# OSO-SCAP-A1-02_SAMD51_Sensor_Cap_WIP.net
KiCad netlist of a schematic drawn in EAGLE
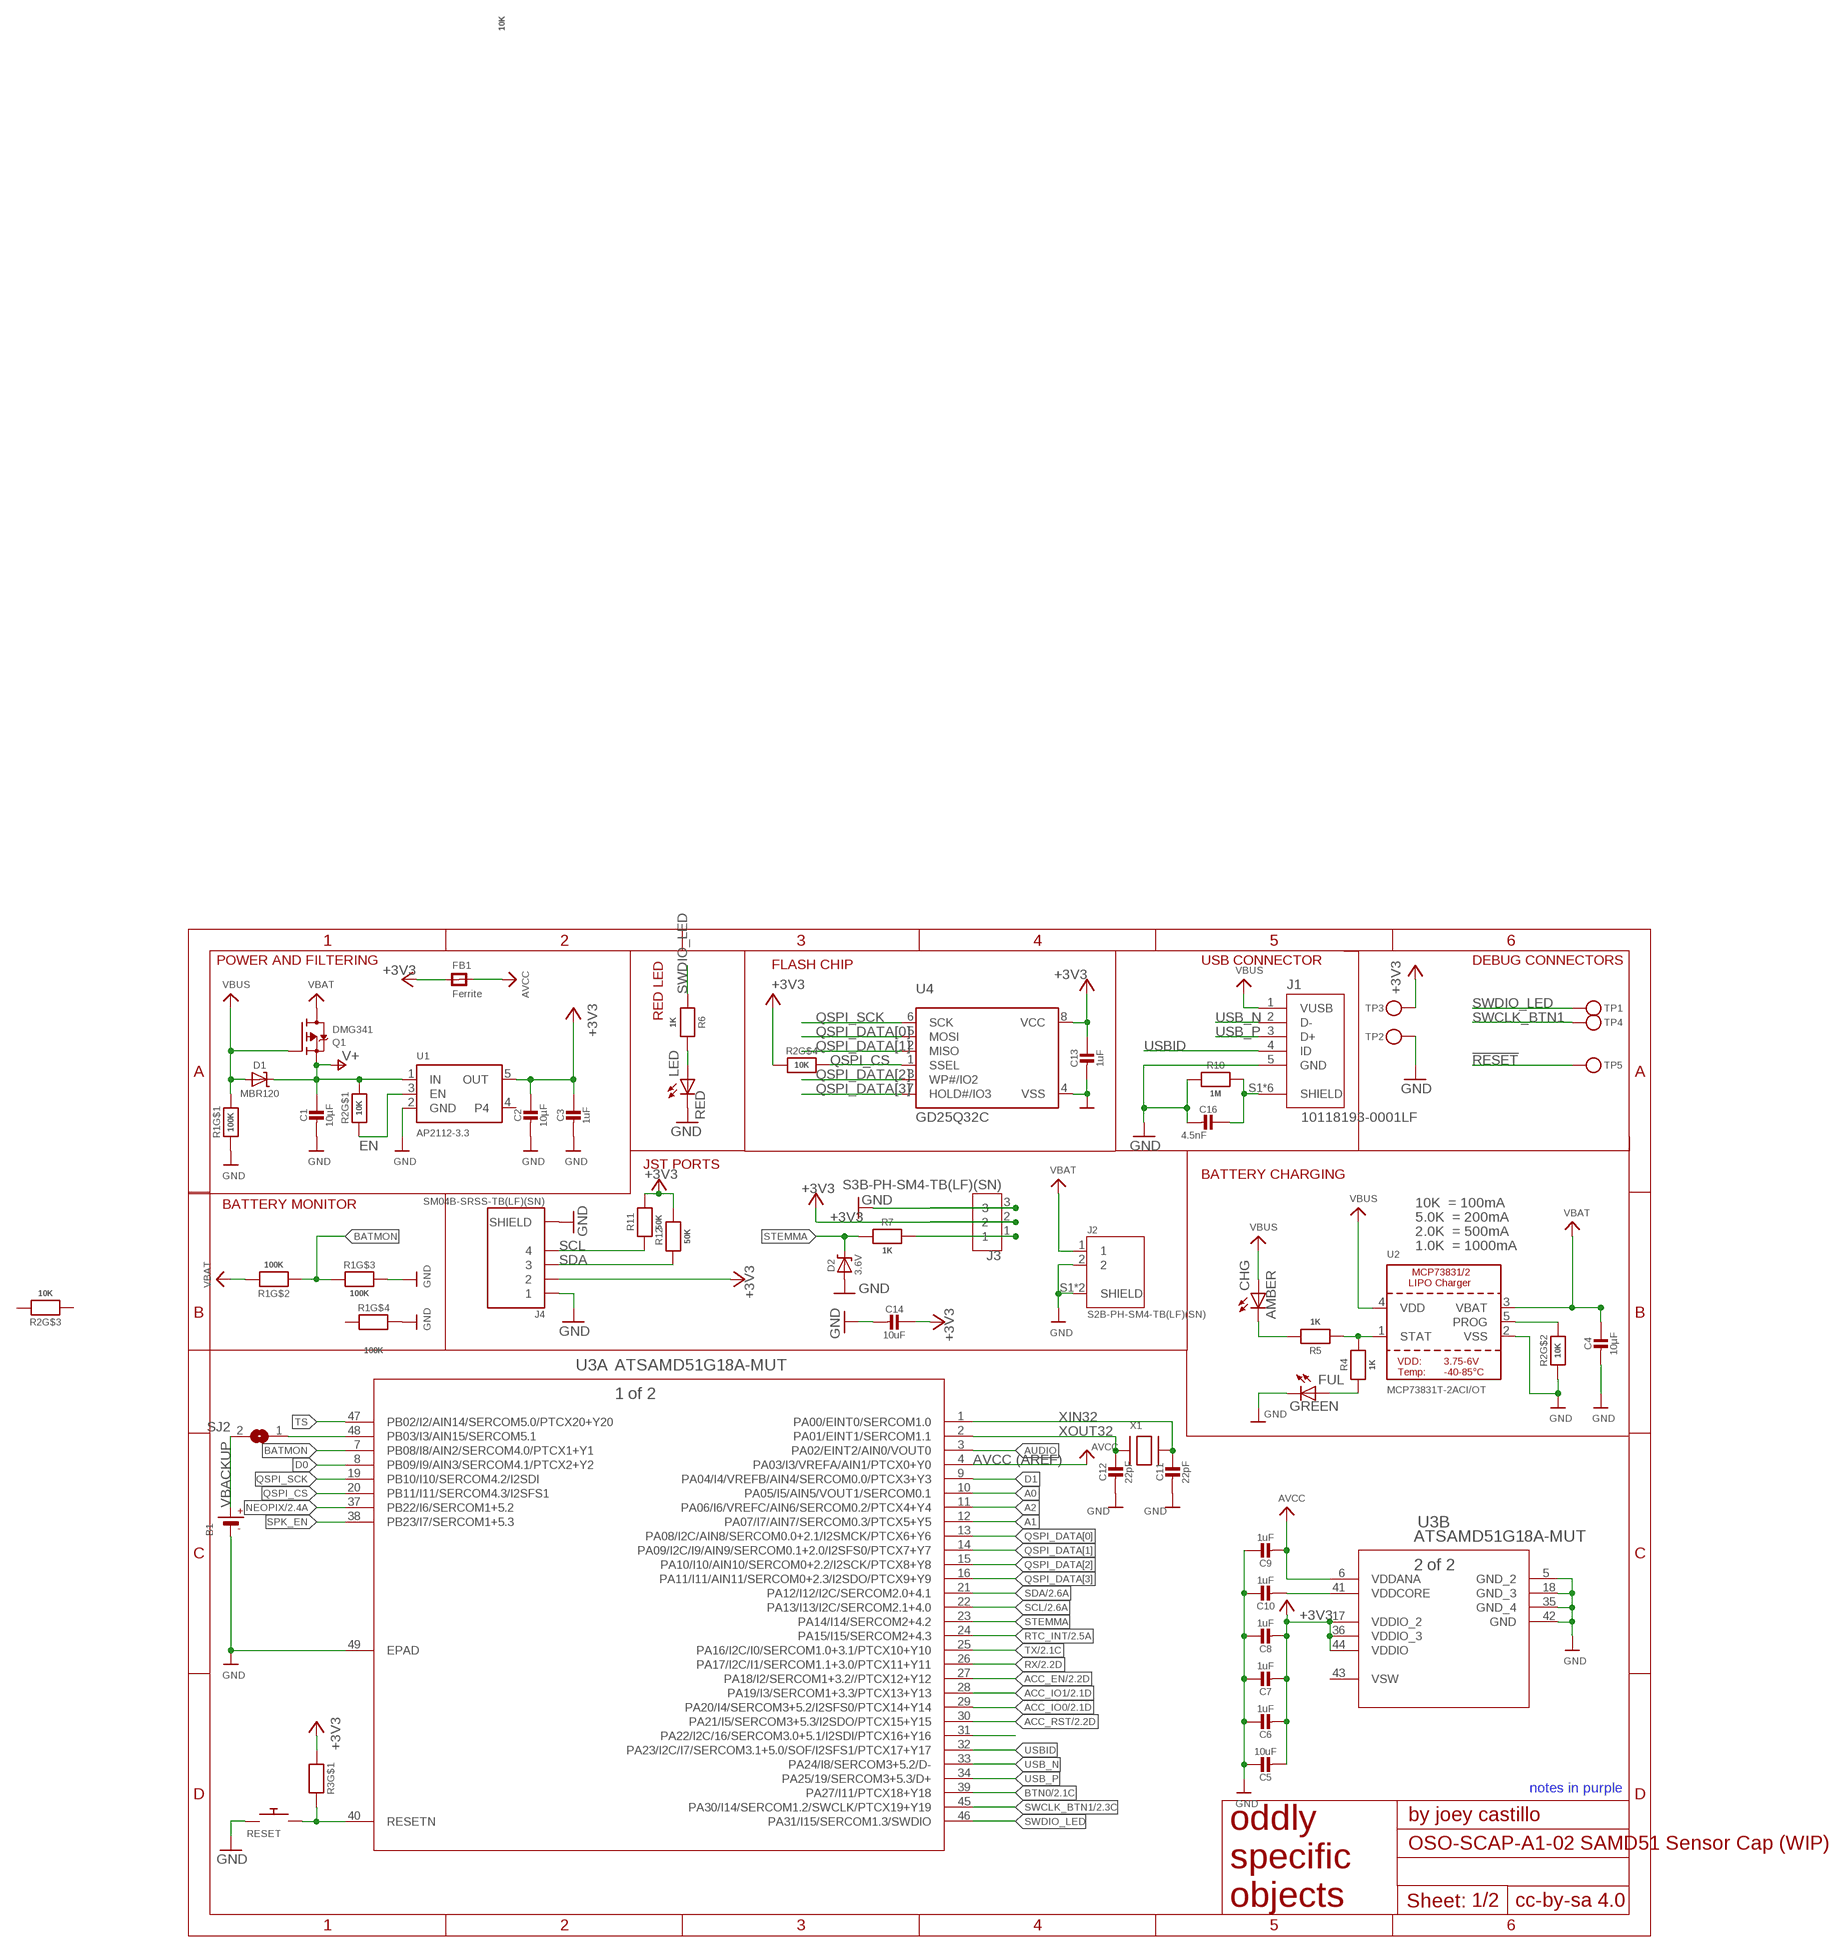
[diagram p0: schematic, sheet 1]
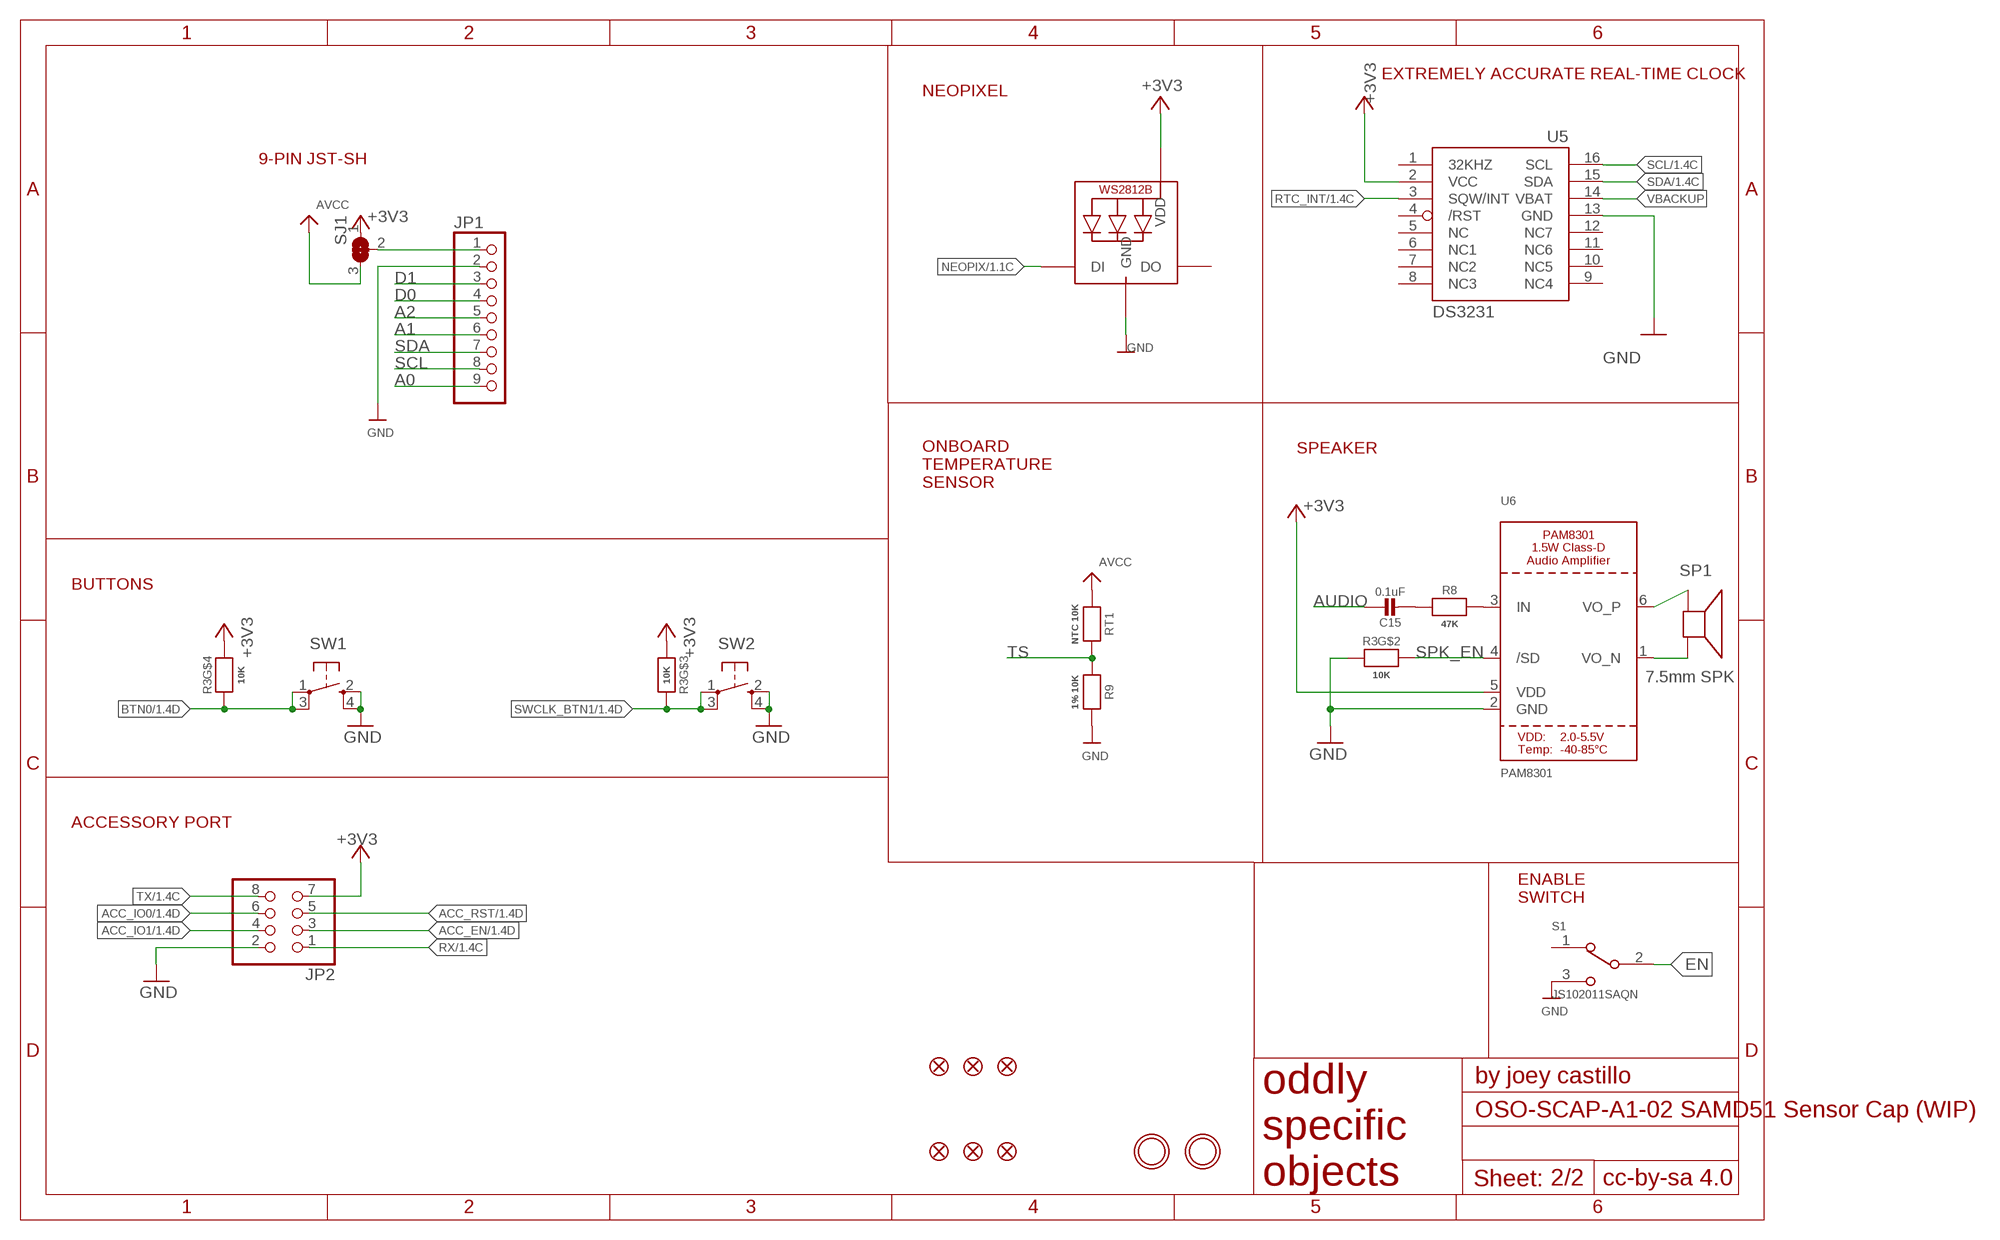
[diagram p1: schematic, sheet 2]

(export (version "E")
  (design (tool "Eeschema 10.0.6"))
  (components
    (comp (ref "B1")
      (value "CR1220")
      (footprint "eagle-import:CR1220-2")
      (libsource (lib "eagle-import") (part "BATTERYCR1220_2"))
    )
    (comp (ref "C1")
      (value "10µF")
      (footprint "eagle-import:0805-NO")
      (libsource (lib "eagle-import") (part "CAP_CERAMIC0805-NOOUTLINE"))
    )
    (comp (ref "C2")
      (value "10µF")
      (footprint "eagle-import:0805-NO")
      (libsource (lib "eagle-import") (part "CAP_CERAMIC0805-NOOUTLINE"))
    )
    (comp (ref "C3")
      (value "1uF")
      (footprint "eagle-import:0805-NO")
      (libsource (lib "eagle-import") (part "CAP_CERAMIC0805-NOOUTLINE"))
    )
    (comp (ref "C4")
      (value "10µF")
      (footprint "eagle-import:0805-NO")
      (libsource (lib "eagle-import") (part "CAP_CERAMIC0805-NOOUTLINE"))
    )
    (comp (ref "C5")
      (value "10uF")
      (footprint "eagle-import:0805_10MGAP")
      (libsource (lib "eagle-import") (part "CAP_CERAMIC0805_10MGAP"))
    )
    (comp (ref "C6")
      (value "1uF")
      (footprint "eagle-import:0805-NO")
      (libsource (lib "eagle-import") (part "CAP_CERAMIC0805-NOOUTLINE"))
    )
    (comp (ref "C7")
      (value "1uF")
      (footprint "eagle-import:0805-NO")
      (libsource (lib "eagle-import") (part "CAP_CERAMIC0805-NOOUTLINE"))
    )
    (comp (ref "C8")
      (value "1uF")
      (footprint "eagle-import:0805-NO")
      (libsource (lib "eagle-import") (part "CAP_CERAMIC0805-NOOUTLINE"))
    )
    (comp (ref "C9")
      (value "1uF")
      (footprint "eagle-import:0805_10MGAP")
      (libsource (lib "eagle-import") (part "CAP_CERAMIC0805_10MGAP"))
    )
    (comp (ref "C10")
      (value "1uF")
      (footprint "eagle-import:0805_10MGAP")
      (libsource (lib "eagle-import") (part "CAP_CERAMIC0805_10MGAP"))
    )
    (comp (ref "C11")
      (value "22pF")
      (footprint "eagle-import:0805-NO")
      (libsource (lib "eagle-import") (part "CAP_CERAMIC0805-NOOUTLINE"))
    )
    (comp (ref "C12")
      (value "22pF")
      (footprint "eagle-import:0805-NO")
      (libsource (lib "eagle-import") (part "CAP_CERAMIC0805-NOOUTLINE"))
    )
    (comp (ref "C13")
      (value "1uF")
      (footprint "eagle-import:0805-NO")
      (libsource (lib "eagle-import") (part "CAP_CERAMIC0805-NOOUTLINE"))
    )
    (comp (ref "C14")
      (value "10uF")
      (footprint "eagle-import:0805-NO")
      (libsource (lib "eagle-import") (part "CAP_CERAMIC0805-NOOUTLINE"))
    )
    (comp (ref "C16")
      (value "4.5nF")
      (footprint "eagle-import:0805-NO")
      (libsource (lib "eagle-import") (part "CAP_CERAMIC0805-NOOUTLINE"))
    )
    (comp (ref "CHG")
      (value "AMBER")
      (footprint "eagle-import:CHIPLED_0603")
      (libsource (lib "eagle-import") (part "LEDCHIPLED_0603"))
    )
    (comp (ref "D1")
      (value "MBR120")
      (footprint "eagle-import:SOD-123")
      (libsource (lib "eagle-import") (part "DIODE-SCHOTTKYSOD-123"))
    )
    (comp (ref "D2")
      (value "3.6V")
      (footprint "eagle-import:SOD-123")
      (libsource (lib "eagle-import") (part "DIODE-ZENERSOD123"))
    )
    (comp (ref "FB1")
      (value "Ferrite")
      (footprint "eagle-import:_0805MP")
      (libsource (lib "eagle-import") (part "FERRITE_0805MP"))
    )
    (comp (ref "FUL")
      (value "GREEN")
      (footprint "eagle-import:CHIPLED_0603")
      (libsource (lib "eagle-import") (part "LEDCHIPLED_0603"))
    )
    (comp (ref "J1")
      (value "10118193-0001LF")
      (footprint "eagle-import:FCI_10118193-0001LF")
      (fields (field (name "DIGI-KEY_PART_NUMBER") "609-4616-1-ND") (field (name "MF") "Amphenol ICC"))
      (libsource (lib "eagle-import") (part "10118193-0001LF"))
    )
    (comp (ref "J2")
      (value "S2B-PH-SM4-TB(LF)(SN)")
      (footprint "eagle-import:JST_S2B-PH-SM4-TB(LF)(SN)")
      (fields
        (field (name "DIGI-KEY_PART_NUMBER") "455-1749-1-ND")
        (field (name "MF") "JST Sales")
        (field (name "MP") "S2B-PH-SM4-TB_LF__SN_")
      )
      (libsource (lib "eagle-import") (part "S2B-PH-SM4-TB(LF)(SN)"))
    )
    (comp (ref "J3")
      (value "S3B-PH-SM4-TB(LF)(SN)")
      (footprint "eagle-import:JST_S3B-PH-SM4-TB(LF)(SN)")
      (fields
        (field (name "DIGI-KEY_PART_NUMBER") "455-1750-1-ND")
        (field (name "MF") "JST Sales")
        (field (name "MP") "S3B-PH-SM4-TB_LF__SN_")
      )
      (libsource (lib "eagle-import") (part "S3B-PH-SM4-TB(LF)(SN)"))
    )
    (comp (ref "J4")
      (value "SM04B-SRSS-TB(LF)(SN)")
      (footprint "eagle-import:JST_SM04B-SRSS-TB(LF)(SN)")
      (fields
        (field (name "DIGI-KEY_PART_NUMBER") "455-1804-1-ND")
        (field (name "MF") "JST Sales")
        (field (name "MP") "SM04B-SRSS-TB_LF__SN_")
      )
      (libsource (lib "eagle-import") (part "SM04B-SRSS-TB(LF)(SN)"))
    )
    (comp (ref "LED")
      (value "RED")
      (footprint "eagle-import:CHIPLED_0805")
      (libsource (lib "eagle-import") (part "LEDCHIPLED_0805"))
    )
    (comp (ref "Q1")
      (value "DMG341")
      (footprint "eagle-import:SOT23-R")
      (libsource (lib "eagle-import") (part "MOSFET-P"))
    )
    (comp (ref "R1")
      (value "100K")
      (footprint "eagle-import:EXBV8V")
      (fields (field (name "MANUFACTURER_PART_NUMBER") "EXBV8V103JV"))
      (libsource (lib "eagle-import") (part "EXB-V8V103JV-GOOD"))
    )
    (comp (ref "R2")
      (value "10K")
      (footprint "eagle-import:EXBV8V")
      (fields (field (name "MANUFACTURER_PART_NUMBER") "EXBV8V103JV"))
      (libsource (lib "eagle-import") (part "EXB-V8V103JV-GOOD"))
    )
    (comp (ref "R3")
      (value "10K")
      (footprint "eagle-import:EXBV8V")
      (fields (field (name "MANUFACTURER_PART_NUMBER") "EXBV8V103JV"))
      (libsource (lib "eagle-import") (part "EXB-V8V103JV-GOOD"))
    )
    (comp (ref "R4")
      (value "1K")
      (footprint "eagle-import:0805-NO")
      (libsource (lib "eagle-import") (part "RESISTOR0805_NOOUTLINE"))
    )
    (comp (ref "R5")
      (value "1K")
      (footprint "eagle-import:0805-NO")
      (libsource (lib "eagle-import") (part "RESISTOR0805_NOOUTLINE"))
    )
    (comp (ref "R6")
      (value "1K")
      (footprint "eagle-import:0805-NO")
      (libsource (lib "eagle-import") (part "RESISTOR0805_NOOUTLINE"))
    )
    (comp (ref "R7")
      (value "1K")
      (footprint "eagle-import:0805-NO")
      (libsource (lib "eagle-import") (part "RESISTOR0805_NOOUTLINE"))
    )
    (comp (ref "R10")
      (value "1M")
      (footprint "eagle-import:0805-NO")
      (libsource (lib "eagle-import") (part "RESISTOR0805_NOOUTLINE"))
    )
    (comp (ref "R11")
      (value "50K")
      (footprint "eagle-import:0805-NO")
      (libsource (lib "eagle-import") (part "RESISTOR0805_NOOUTLINE"))
    )
    (comp (ref "R12")
      (value "50K")
      (footprint "eagle-import:0805-NO")
      (libsource (lib "eagle-import") (part "RESISTOR0805_NOOUTLINE"))
    )
    (comp (ref "RESET")
      (value "SWITCH_PUSHBUTTONC&K_KSS")
      (footprint "eagle-import:BTN_CK_KSS")
      (libsource (lib "eagle-import") (part "SWITCH_PUSHBUTTONC&K_KSS"))
    )
    (comp (ref "SJ2")
      (value "SOLDERJUMPERREFLOW_NOPASTE")
      (footprint "eagle-import:SOLDERJUMPER_REFLOW_NOPASTE")
      (libsource (lib "eagle-import") (part "SOLDERJUMPERREFLOW_NOPASTE"))
    )
    (comp (ref "TP1")
      (value "TESTPOINTROUND1.5MMNO")
      (footprint "eagle-import:TESTPOINT_ROUND_1.5MM_NO")
      (libsource (lib "eagle-import") (part "TESTPOINTROUND1.5MMNO"))
    )
    (comp (ref "TP2")
      (value "TESTPOINTROUND1.5MMNO")
      (footprint "eagle-import:TESTPOINT_ROUND_1.5MM_NO")
      (libsource (lib "eagle-import") (part "TESTPOINTROUND1.5MMNO"))
    )
    (comp (ref "TP3")
      (value "TESTPOINTROUND1.5MMNO")
      (footprint "eagle-import:TESTPOINT_ROUND_1.5MM_NO")
      (libsource (lib "eagle-import") (part "TESTPOINTROUND1.5MMNO"))
    )
    (comp (ref "TP4")
      (value "TESTPOINTROUND1.5MMNO")
      (footprint "eagle-import:TESTPOINT_ROUND_1.5MM_NO")
      (libsource (lib "eagle-import") (part "TESTPOINTROUND1.5MMNO"))
    )
    (comp (ref "TP5")
      (value "TESTPOINTROUND1.5MMNO")
      (footprint "eagle-import:TESTPOINT_ROUND_1.5MM_NO")
      (libsource (lib "eagle-import") (part "TESTPOINTROUND1.5MMNO"))
    )
    (comp (ref "U1")
      (value "AP2112-3.3")
      (footprint "eagle-import:SOT23-5")
      (libsource (lib "eagle-import") (part "VREG_SOT23-5"))
    )
    (comp (ref "U2")
      (value "MCP73831T-2ACI/OT")
      (footprint "eagle-import:SOT23-5")
      (libsource (lib "eagle-import") (part "MCP73831/2"))
    )
    (comp (ref "U3")
      (value "ATSAMD51G18A-MUT")
      (footprint "eagle-import:QFN48_7X7MC")
      (fields (field (name "COPYRIGHT") "Copyright (C) 2018 Accelerated Designs. All rights reserved"))
      (libsource (lib "eagle-import") (part "ATSAMD51G18A-MUT"))
    )
    (comp (ref "U4")
      (value "GD25Q32C")
      (footprint "eagle-import:MICROBUILDER_SOIC8_150MIL")
      (libsource (lib "eagle-import") (part "MICROBUILDER_SPIFLASH_SOIC8"))
    )
    (comp (ref "X1")
      (value "XTAL-3.2X1.5")
      (footprint "eagle-import:XTAL3215")
      (libsource (lib "eagle-import") (part "XTAL-3.2X1.5"))
    )
    (comp (ref "C15")
      (value "0.1uF")
      (footprint "eagle-import:0805-NO")
      (libsource (lib "eagle-import") (part "CAP_CERAMIC0805-NOOUTLINE"))
    )
    (comp (ref "FID1")
      (value "FIDUCIAL_1MM")
      (footprint "eagle-import:FIDUCIAL_1MM")
      (libsource (lib "eagle-import") (part "FIDUCIAL_1MM"))
    )
    (comp (ref "FID2")
      (value "FIDUCIAL_1MM")
      (footprint "eagle-import:FIDUCIAL_1MM")
      (libsource (lib "eagle-import") (part "FIDUCIAL_1MM"))
    )
    (comp (ref "FID3")
      (value "FIDUCIAL_1MM")
      (footprint "eagle-import:FIDUCIAL_1MM")
      (libsource (lib "eagle-import") (part "FIDUCIAL_1MM"))
    )
    (comp (ref "FID4")
      (value "FIDUCIAL_1MM")
      (footprint "eagle-import:FIDUCIAL_1MM")
      (libsource (lib "eagle-import") (part "FIDUCIAL_1MM"))
    )
    (comp (ref "FID5")
      (value "FIDUCIAL_1MM")
      (footprint "eagle-import:FIDUCIAL_1MM")
      (libsource (lib "eagle-import") (part "FIDUCIAL_1MM"))
    )
    (comp (ref "FID6")
      (value "FIDUCIAL_1MM")
      (footprint "eagle-import:FIDUCIAL_1MM")
      (libsource (lib "eagle-import") (part "FIDUCIAL_1MM"))
    )
    (comp (ref "JP1")
      (value "HEADER-1X9_JSTSH")
      (footprint "eagle-import:JST_SH9")
      (libsource (lib "eagle-import") (part "HEADER-1X9_JSTSH"))
    )
    (comp (ref "JP2")
      (value "PINHD-2X4SMT")
      (footprint "eagle-import:PINHD_2X4_SMT")
      (libsource (lib "eagle-import") (part "PINHD-2X4SMT"))
    )
    (comp (ref "NEOPIX")
      (value "WS2812B_4020")
      (footprint "eagle-import:WS2812B_4020")
      (libsource (lib "eagle-import") (part "WS2812B_4020"))
    )
    (comp (ref "R8")
      (value "47K")
      (footprint "eagle-import:0805-NO")
      (libsource (lib "eagle-import") (part "RESISTOR0805_NOOUTLINE"))
    )
    (comp (ref "R9")
      (value "1% 10K")
      (footprint "eagle-import:0805-NO")
      (libsource (lib "eagle-import") (part "RESISTOR0805_NOOUTLINE"))
    )
    (comp (ref "RT1")
      (value "NTC 10K")
      (footprint "eagle-import:0805-NO")
      (libsource (lib "eagle-import") (part "RESISTOR0805_NOOUTLINE"))
    )
    (comp (ref "S1")
      (value "JS102011SAQN")
      (footprint "eagle-import:SW_JS102011SAQN")
      (fields (field (name "DIGI-KEY_PART_NUMBER") "401-1999-1-ND") (field (name "MF") "C&K"))
      (libsource (lib "eagle-import") (part "JS102011SAQN"))
    )
    (comp (ref "SJ1")
      (value "SOLDERJUMPER_2WAY")
      (footprint "eagle-import:SOLDERJUMPER_2WAY_OPEN_NOPASTE")
      (libsource (lib "eagle-import") (part "SOLDERJUMPER_2WAY"))
    )
    (comp (ref "SP1")
      (value "7.5mm SPK")
      (footprint "eagle-import:BUZZER_SMT_5MM")
      (libsource (lib "eagle-import") (part "SPEAKER_BUZZER5MM"))
    )
    (comp (ref "SW1")
      (value "SPST_TACT-KMR2")
      (footprint "eagle-import:KMR2")
      (libsource (lib "eagle-import") (part "SPST_TACT-KMR2"))
    )
    (comp (ref "SW2")
      (value "SPST_TACT-KMR2")
      (footprint "eagle-import:KMR2")
      (libsource (lib "eagle-import") (part "SPST_TACT-KMR2"))
    )
    (comp (ref "U$1")
      (value "MOUNTINGHOLE2.5")
      (footprint "eagle-import:MOUNTINGHOLE_2.5_PLATED")
      (libsource (lib "eagle-import") (part "MOUNTINGHOLE2.5"))
    )
    (comp (ref "U$4")
      (value "MOUNTINGHOLE2.5")
      (footprint "eagle-import:MOUNTINGHOLE_2.5_PLATED")
      (libsource (lib "eagle-import") (part "MOUNTINGHOLE2.5"))
    )
    (comp (ref "U5")
      (value "DS3231/SO")
      (footprint "eagle-import:SO16W")
      (libsource (lib "eagle-import") (part "DS3231/SO"))
    )
    (comp (ref "U6")
      (value "PAM8301")
      (footprint "eagle-import:SOT23-6")
      (libsource (lib "eagle-import") (part "PAM8301"))
    )
  )
  (nets
    (net (code "1") (name "+3V3") (class "Default")
      (node (ref "C13") (pin "1") (pinfunction "1_1") (pintype "passive"))
      (node (ref "C14") (pin "1") (pinfunction "1_1") (pintype "passive"))
      (node (ref "C2") (pin "1") (pinfunction "1_1") (pintype "passive"))
      (node (ref "C3") (pin "1") (pinfunction "1_1") (pintype "passive"))
      (node (ref "C5") (pin "2") (pinfunction "2_2") (pintype "passive"))
      (node (ref "C6") (pin "2") (pinfunction "2_2") (pintype "passive"))
      (node (ref "C7") (pin "2") (pinfunction "2_2") (pintype "passive"))
      (node (ref "C8") (pin "2") (pinfunction "2_2") (pintype "passive"))
      (node (ref "FB1") (pin "1") (pinfunction "P$1_1") (pintype "passive"))
      (node (ref "J3") (pin "2") (pinfunction "2_2") (pintype "passive"))
      (node (ref "J4") (pin "2") (pinfunction "2_2") (pintype "passive"))
      (node (ref "JP2") (pin "7") (pinfunction "7_7") (pintype "passive"))
      (node (ref "NEOPIX") (pin "2") (pinfunction "VDD_2") (pintype "power_in"))
      (node (ref "R11") (pin "2") (pinfunction "2_2") (pintype "passive"))
      (node (ref "R12") (pin "2") (pinfunction "2_2") (pintype "passive"))
      (node (ref "R2") (pin "4") (pinfunction "1_4") (pintype "passive"))
      (node (ref "R3") (pin "1") (pinfunction "1_1") (pintype "passive"))
      (node (ref "R3") (pin "3") (pinfunction "1_3") (pintype "passive"))
      (node (ref "R3") (pin "5") (pinfunction "2_5") (pintype "passive"))
      (node (ref "SJ1") (pin "1") (pinfunction "1_1") (pintype "passive"))
      (node (ref "TP3") (pin "P$1") (pinfunction "P$1_P$1") (pintype "bidirectional"))
      (node (ref "U1") (pin "5") (pinfunction "OUT_5") (pintype "power_in"))
      (node (ref "U3") (pin "17") (pinfunction "VDDIO_2_17") (pintype "power_in"))
      (node (ref "U3") (pin "36") (pinfunction "VDDIO_3_36") (pintype "power_in"))
      (node (ref "U3") (pin "44") (pinfunction "VDDIO_44") (pintype "power_in"))
      (node (ref "U4") (pin "8") (pinfunction "VCC_8") (pintype "bidirectional"))
      (node (ref "U5") (pin "2") (pinfunction "VCC_2") (pintype "power_in"))
      (node (ref "U6") (pin "5") (pinfunction "VDD_5") (pintype "power_in"))
    )
    (net (code "2") (name "A0") (class "Default")
      (node (ref "JP1") (pin "9") (pinfunction "9_9") (pintype "passive"))
      (node (ref "U3") (pin "10") (pinfunction "PA05/I5/AIN5/VOUT1/SERCOM0.1_10") (pintype "bidirectional"))
    )
    (net (code "3") (name "A1") (class "Default")
      (node (ref "JP1") (pin "6") (pinfunction "6_6") (pintype "passive"))
      (node (ref "U3") (pin "12") (pinfunction "PA07/I7/AIN7/SERCOM0.3/PTCX5+Y5_12") (pintype "bidirectional"))
    )
    (net (code "4") (name "A2") (class "Default")
      (node (ref "JP1") (pin "5") (pinfunction "5_5") (pintype "passive"))
      (node (ref "U3") (pin "11") (pinfunction "PA06/I6/VREFC/AIN6/SERCOM0.2/PTCX4+Y4_11") (pintype "bidirectional"))
    )
    (net (code "5") (name "ACC_EN") (class "Default")
      (node (ref "JP2") (pin "3") (pinfunction "3_3") (pintype "passive"))
      (node (ref "U3") (pin "27") (pinfunction "PA18/I2/SERCOM1+3.2//PTCX12+Y12_27") (pintype "bidirectional"))
    )
    (net (code "6") (name "ACC_IO0") (class "Default")
      (node (ref "JP2") (pin "6") (pinfunction "6_6") (pintype "passive"))
      (node (ref "U3") (pin "29") (pinfunction "PA20/I4/SERCOM3+5.2/I2SFS0/PTCX14+Y14_29") (pintype "bidirectional"))
    )
    (net (code "7") (name "ACC_IO1") (class "Default")
      (node (ref "JP2") (pin "4") (pinfunction "4_4") (pintype "passive"))
      (node (ref "U3") (pin "28") (pinfunction "PA19/I3/SERCOM1+3.3/PTCX13+Y13_28") (pintype "bidirectional"))
    )
    (net (code "8") (name "ACC_RST") (class "Default")
      (node (ref "JP2") (pin "5") (pinfunction "5_5") (pintype "passive"))
      (node (ref "U3") (pin "30") (pinfunction "PA21/I5/SERCOM3+5.3/I2SDO/PTCX15+Y15_30") (pintype "bidirectional"))
    )
    (net (code "9") (name "AUDIO") (class "Default")
      (node (ref "C15") (pin "1") (pinfunction "1_1") (pintype "passive"))
      (node (ref "U3") (pin "3") (pinfunction "PA02/EINT2/AIN0/VOUT0_3") (pintype "bidirectional"))
    )
    (net (code "10") (name "AVCC") (class "Default")
      (node (ref "C9") (pin "2") (pinfunction "2_2") (pintype "passive"))
      (node (ref "FB1") (pin "2") (pinfunction "P$2_2") (pintype "passive"))
      (node (ref "RT1") (pin "1") (pinfunction "1_1") (pintype "passive"))
      (node (ref "SJ1") (pin "3") (pinfunction "3_3") (pintype "passive"))
      (node (ref "U3") (pin "4") (pinfunction "PA03/I3/VREFA/AIN1/PTCX0+Y0_4") (pintype "bidirectional"))
      (node (ref "U3") (pin "6") (pinfunction "VDDANA_6") (pintype "power_in"))
    )
    (net (code "11") (name "BATMON") (class "Default")
      (node (ref "R1") (pin "2") (pinfunction "1_2") (pintype "passive"))
      (node (ref "R1") (pin "3") (pinfunction "1_3") (pintype "passive"))
      (node (ref "U3") (pin "7") (pinfunction "PB08/I8/AIN2/SERCOM4.0/PTCX1+Y1_7") (pintype "bidirectional"))
    )
    (net (code "12") (name "BTN0") (class "Default")
      (node (ref "R3") (pin "4") (pinfunction "1_4") (pintype "passive"))
      (node (ref "SW1") (pin "1") (pinfunction "P_1") (pintype "passive"))
      (node (ref "SW1") (pin "3") (pinfunction "P1_3") (pintype "passive"))
      (node (ref "U3") (pin "39") (pinfunction "PA27/I11/PTCX18+Y18_39") (pintype "bidirectional"))
    )
    (net (code "13") (name "D0") (class "Default")
      (node (ref "JP1") (pin "4") (pinfunction "4_4") (pintype "passive"))
      (node (ref "U3") (pin "8") (pinfunction "PB09/I9/AIN3/SERCOM4.1/PTCX2+Y2_8") (pintype "bidirectional"))
    )
    (net (code "14") (name "D1") (class "Default")
      (node (ref "JP1") (pin "3") (pinfunction "3_3") (pintype "passive"))
      (node (ref "U3") (pin "9") (pinfunction "PA04/I4/VREFB/AIN4/SERCOM0.0/PTCX3+Y3_9") (pintype "bidirectional"))
    )
    (net (code "15") (name "EN") (class "Default")
      (node (ref "R2") (pin "1") (pinfunction "1_1") (pintype "passive"))
      (node (ref "S1") (pin "2") (pinfunction "2_2") (pintype "passive"))
      (node (ref "U1") (pin "3") (pinfunction "EN_3") (pintype "input"))
    )
    (net (code "16") (name "GND") (class "Default")
      (node (ref "B1") (pin "-") (pinfunction "-_-") (pintype "passive"))
      (node (ref "C1") (pin "2") (pinfunction "2_2") (pintype "passive"))
      (node (ref "C10") (pin "1") (pinfunction "1_1") (pintype "passive"))
      (node (ref "C11") (pin "2") (pinfunction "2_2") (pintype "passive"))
      (node (ref "C12") (pin "2") (pinfunction "2_2") (pintype "passive"))
      (node (ref "C13") (pin "2") (pinfunction "2_2") (pintype "passive"))
      (node (ref "C14") (pin "2") (pinfunction "2_2") (pintype "passive"))
      (node (ref "C16") (pin "2") (pinfunction "2_2") (pintype "passive"))
      (node (ref "C2") (pin "2") (pinfunction "2_2") (pintype "passive"))
      (node (ref "C3") (pin "2") (pinfunction "2_2") (pintype "passive"))
      (node (ref "C4") (pin "2") (pinfunction "2_2") (pintype "passive"))
      (node (ref "C5") (pin "1") (pinfunction "1_1") (pintype "passive"))
      (node (ref "C6") (pin "1") (pinfunction "1_1") (pintype "passive"))
      (node (ref "C7") (pin "1") (pinfunction "1_1") (pintype "passive"))
      (node (ref "C8") (pin "1") (pinfunction "1_1") (pintype "passive"))
      (node (ref "C9") (pin "1") (pinfunction "1_1") (pintype "passive"))
      (node (ref "D2") (pin "A") (pinfunction "A_A") (pintype "passive"))
      (node (ref "FUL") (pin "C") (pinfunction "C_C") (pintype "passive"))
      (node (ref "J1") (pin "5") (pinfunction "GND_5") (pintype "passive"))
      (node (ref "J2") (pin "2") (pinfunction "2_2") (pintype "passive"))
      (node (ref "J2") (pin "S1") (pinfunction "SHIELD_S1") (pintype "passive"))
      (node (ref "J2") (pin "S2") (pinfunction "SHIELD_S2") (pintype "passive"))
      (node (ref "J3") (pin "3") (pinfunction "3_3") (pintype "passive"))
      (node (ref "J4") (pin "1") (pinfunction "1_1") (pintype "passive"))
      (node (ref "J4") (pin "S1") (pinfunction "SHIELD_S1") (pintype "passive"))
      (node (ref "J4") (pin "S2") (pinfunction "SHIELD_S2") (pintype "passive"))
      (node (ref "JP1") (pin "2") (pinfunction "2_2") (pintype "passive"))
      (node (ref "JP2") (pin "2") (pinfunction "2_2") (pintype "passive"))
      (node (ref "LED") (pin "C") (pinfunction "C_C") (pintype "passive"))
      (node (ref "NEOPIX") (pin "4") (pinfunction "GND_4") (pintype "power_in"))
      (node (ref "R1") (pin "1") (pinfunction "1_1") (pintype "passive"))
      (node (ref "R1") (pin "5") (pinfunction "2_5") (pintype "passive"))
      (node (ref "R1") (pin "6") (pinfunction "2_6") (pintype "passive"))
      (node (ref "R10") (pin "2") (pinfunction "2_2") (pintype "passive"))
      (node (ref "R2") (pin "2") (pinfunction "1_2") (pintype "passive"))
      (node (ref "R3") (pin "2") (pinfunction "1_2") (pintype "passive"))
      (node (ref "R9") (pin "2") (pinfunction "2_2") (pintype "passive"))
      (node (ref "RESET") (pin "P$1") (pinfunction "P$1_P$1") (pintype "passive"))
      (node (ref "S1") (pin "3") (pinfunction "3_3") (pintype "passive"))
      (node (ref "SW1") (pin "2") (pinfunction "S_2") (pintype "passive"))
      (node (ref "SW1") (pin "4") (pinfunction "S1_4") (pintype "passive"))
      (node (ref "SW2") (pin "2") (pinfunction "S_2") (pintype "passive"))
      (node (ref "SW2") (pin "4") (pinfunction "S1_4") (pintype "passive"))
      (node (ref "TP2") (pin "P$1") (pinfunction "P$1_P$1") (pintype "bidirectional"))
      (node (ref "U1") (pin "2") (pinfunction "GND_2") (pintype "power_in"))
      (node (ref "U2") (pin "2") (pinfunction "VSS_2") (pintype "power_in"))
      (node (ref "U3") (pin "18") (pinfunction "GND_3_18") (pintype "passive"))
      (node (ref "U3") (pin "35") (pinfunction "GND_4_35") (pintype "passive"))
      (node (ref "U3") (pin "42") (pinfunction "GND_42") (pintype "passive"))
      (node (ref "U3") (pin "49") (pinfunction "EPAD_49") (pintype "passive"))
      (node (ref "U3") (pin "5") (pinfunction "GND_2_5") (pintype "passive"))
      (node (ref "U4") (pin "4") (pinfunction "VSS_4") (pintype "bidirectional"))
      (node (ref "U5") (pin "13") (pinfunction "GND_13") (pintype "power_in"))
      (node (ref "U6") (pin "2") (pinfunction "GND_2") (pintype "power_in"))
    )
    (net (code "17") (name "NEOPIX") (class "Default")
      (node (ref "NEOPIX") (pin "1") (pinfunction "DI_1") (pintype "input"))
      (node (ref "U3") (pin "37") (pinfunction "PB22/I6/SERCOM1+5.2_37") (pintype "bidirectional"))
    )
    (net (code "18") (name "Net-(C15-Pad2)") (class "Default")
      (node (ref "C15") (pin "2") (pinfunction "2_2") (pintype "passive"))
      (node (ref "R8") (pin "1") (pinfunction "1_1") (pintype "passive"))
    )
    (net (code "19") (name "Net-(C16-Pad1)") (class "Default")
      (node (ref "C16") (pin "1") (pinfunction "1_1") (pintype "passive"))
      (node (ref "J1") (pin "S1") (pinfunction "SHIELD_S1") (pintype "passive"))
      (node (ref "J1") (pin "S2") (pinfunction "SHIELD_S2") (pintype "passive"))
      (node (ref "J1") (pin "S3") (pinfunction "SHIELD_S3") (pintype "passive"))
      (node (ref "J1") (pin "S4") (pinfunction "SHIELD_S4") (pintype "passive"))
      (node (ref "J1") (pin "S5") (pinfunction "SHIELD_S5") (pintype "passive"))
      (node (ref "J1") (pin "S6") (pinfunction "SHIELD_S6") (pintype "passive"))
      (node (ref "R10") (pin "1") (pinfunction "1_1") (pintype "passive"))
    )
    (net (code "20") (name "Net-(CHG-PadC)") (class "Default")
      (node (ref "CHG") (pin "C") (pinfunction "C_C") (pintype "passive"))
      (node (ref "R5") (pin "2") (pinfunction "2_2") (pintype "passive"))
    )
    (net (code "21") (name "Net-(FUL-PadA)") (class "Default")
      (node (ref "FUL") (pin "A") (pinfunction "A_A") (pintype "passive"))
      (node (ref "R4") (pin "1") (pinfunction "1_1") (pintype "passive"))
    )
    (net (code "22") (name "Net-(J3-Pad1)") (class "Default")
      (node (ref "J3") (pin "1") (pinfunction "1_1") (pintype "passive"))
      (node (ref "R7") (pin "1") (pinfunction "1_1") (pintype "passive"))
    )
    (net (code "23") (name "Net-(JP1-Pad1)") (class "Default")
      (node (ref "JP1") (pin "1") (pinfunction "1_1") (pintype "passive"))
      (node (ref "SJ1") (pin "2") (pinfunction "2_2") (pintype "passive"))
    )
    (net (code "24") (name "Net-(LED-PadA)") (class "Default")
      (node (ref "LED") (pin "A") (pinfunction "A_A") (pintype "passive"))
      (node (ref "R6") (pin "2") (pinfunction "2_2") (pintype "passive"))
    )
    (net (code "25") (name "Net-(R2B-2)") (class "Default")
      (node (ref "R2") (pin "7") (pinfunction "2_7") (pintype "passive"))
      (node (ref "U2") (pin "5") (pinfunction "PROG_5") (pintype "input"))
    )
    (net (code "26") (name "Net-(U2-STAT)") (class "Default")
      (node (ref "R4") (pin "2") (pinfunction "2_2") (pintype "passive"))
      (node (ref "R5") (pin "1") (pinfunction "1_1") (pintype "passive"))
      (node (ref "U2") (pin "1") (pinfunction "STAT_1") (pintype "output"))
    )
    (net (code "27") (name "Net-(U3A-PB03{slash}I3{slash}AIN15{slash}SERCOM5.1)") (class "Default")
      (node (ref "SJ2") (pin "1") (pinfunction "1_1") (pintype "passive"))
      (node (ref "U3") (pin "48") (pinfunction "PB03/I3/AIN15/SERCOM5.1_48") (pintype "bidirectional"))
    )
    (net (code "28") (name "Net-(U3B-VDDCORE)") (class "Default")
      (node (ref "C10") (pin "2") (pinfunction "2_2") (pintype "passive"))
      (node (ref "U3") (pin "41") (pinfunction "VDDCORE_41") (pintype "bidirectional"))
    )
    (net (code "29") (name "Net-(U6-IN)") (class "Default")
      (node (ref "R8") (pin "2") (pinfunction "2_2") (pintype "passive"))
      (node (ref "U6") (pin "3") (pinfunction "IN_3") (pintype "input"))
    )
    (net (code "30") (name "Net-(U6-VO_N)") (class "Default")
      (node (ref "SP1") (pin "+") (pinfunction "+_+") (pintype "passive"))
      (node (ref "U6") (pin "1") (pinfunction "VO_N_1") (pintype "output"))
    )
    (net (code "31") (name "Net-(U6-VO_P)") (class "Default")
      (node (ref "SP1") (pin "-") (pinfunction "-_-") (pintype "passive"))
      (node (ref "U6") (pin "6") (pinfunction "VO_P_6") (pintype "output"))
    )
    (net (code "32") (name "QSPI_CS") (class "Default")
      (node (ref "R2") (pin "5") (pinfunction "2_5") (pintype "passive"))
      (node (ref "U3") (pin "20") (pinfunction "PB11/I11/SERCOM4.3/I2SFS1_20") (pintype "bidirectional"))
      (node (ref "U4") (pin "1") (pinfunction "SSEL_1") (pintype "bidirectional"))
    )
    (net (code "33") (name "QSPI_DATA[0]") (class "Default")
      (node (ref "U3") (pin "13") (pinfunction "PA08/I2C/AIN8/SERCOM0.0+2.1/I2SMCK/PTCX6+Y6_13") (pintype "bidirectional"))
      (node (ref "U4") (pin "5") (pinfunction "MOSI_5") (pintype "bidirectional"))
    )
    (net (code "34") (name "QSPI_DATA[1]") (class "Default")
      (node (ref "U3") (pin "14") (pinfunction "PA09/I2C/I9/AIN9/SERCOM0.1+2.0/I2SFS0/PTCX7+Y7_14") (pintype "bidirectional"))
      (node (ref "U4") (pin "2") (pinfunction "MISO_2") (pintype "bidirectional"))
    )
    (net (code "35") (name "QSPI_DATA[2]") (class "Default")
      (node (ref "U3") (pin "15") (pinfunction "PA10/I10/AIN10/SERCOM0+2.2/I2SCK/PTCX8+Y8_15") (pintype "bidirectional"))
      (node (ref "U4") (pin "3") (pinfunction "WP#/IO2_3") (pintype "bidirectional"))
    )
    (net (code "36") (name "QSPI_DATA[3]") (class "Default")
      (node (ref "U3") (pin "16") (pinfunction "PA11/I11/AIN11/SERCOM0+2.3/I2SDO/PTCX9+Y9_16") (pintype "bidirectional"))
      (node (ref "U4") (pin "7") (pinfunction "HOLD#/IO3_7") (pintype "bidirectional"))
    )
    (net (code "37") (name "QSPI_SCK") (class "Default")
      (node (ref "U3") (pin "19") (pinfunction "PB10/I10/SERCOM4.2/I2SDI_19") (pintype "bidirectional"))
      (node (ref "U4") (pin "6") (pinfunction "SCK_6") (pintype "bidirectional"))
    )
    (net (code "38") (name "RTC_INT") (class "Default")
      (node (ref "U3") (pin "24") (pinfunction "PA15/I15/SERCOM2+4.3_24") (pintype "bidirectional"))
      (node (ref "U5") (pin "3") (pinfunction "SQW/INT_3") (pintype "output"))
    )
    (net (code "39") (name "RX") (class "Default")
      (node (ref "JP2") (pin "1") (pinfunction "1_1") (pintype "passive"))
      (node (ref "U3") (pin "26") (pinfunction "PA17/I2C/I1/SERCOM1.1+3.0/PTCX11+Y11_26") (pintype "bidirectional"))
    )
    (net (code "40") (name "SCL") (class "Default")
      (node (ref "J4") (pin "4") (pinfunction "4_4") (pintype "passive"))
      (node (ref "JP1") (pin "8") (pinfunction "8_8") (pintype "passive"))
      (node (ref "R11") (pin "1") (pinfunction "1_1") (pintype "passive"))
      (node (ref "U3") (pin "22") (pinfunction "PA13/I13/I2C/SERCOM2.1+4.0_22") (pintype "bidirectional"))
      (node (ref "U5") (pin "16") (pinfunction "SCL_16") (pintype "bidirectional"))
    )
    (net (code "41") (name "SDA") (class "Default")
      (node (ref "J4") (pin "3") (pinfunction "3_3") (pintype "passive"))
      (node (ref "JP1") (pin "7") (pinfunction "7_7") (pintype "passive"))
      (node (ref "R12") (pin "1") (pinfunction "1_1") (pintype "passive"))
      (node (ref "U3") (pin "21") (pinfunction "PA12/I12/I2C/SERCOM2.0+4.1_21") (pintype "bidirectional"))
      (node (ref "U5") (pin "15") (pinfunction "SDA_15") (pintype "bidirectional"))
    )
    (net (code "42") (name "SPK_EN") (class "Default")
      (node (ref "R3") (pin "7") (pinfunction "2_7") (pintype "passive"))
      (node (ref "U3") (pin "38") (pinfunction "PB23/I7/SERCOM1+5.3_38") (pintype "bidirectional"))
      (node (ref "U6") (pin "4") (pinfunction "/SD_4") (pintype "input"))
    )
    (net (code "43") (name "STEMMA") (class "Default")
      (node (ref "D2") (pin "C") (pinfunction "C_C") (pintype "passive"))
      (node (ref "R7") (pin "2") (pinfunction "2_2") (pintype "passive"))
      (node (ref "U3") (pin "23") (pinfunction "PA14/I14/SERCOM2+4.2_23") (pintype "bidirectional"))
    )
    (net (code "44") (name "SWCLK_BTN1") (class "Default")
      (node (ref "R3") (pin "6") (pinfunction "2_6") (pintype "passive"))
      (node (ref "SW2") (pin "1") (pinfunction "P_1") (pintype "passive"))
      (node (ref "SW2") (pin "3") (pinfunction "P1_3") (pintype "passive"))
      (node (ref "TP4") (pin "P$1") (pinfunction "P$1_P$1") (pintype "bidirectional"))
      (node (ref "U3") (pin "45") (pinfunction "PA30/I14/SERCOM1.2/SWCLK/PTCX19+Y19_45") (pintype "bidirectional"))
    )
    (net (code "45") (name "SWDIO_LED") (class "Default")
      (node (ref "R6") (pin "1") (pinfunction "1_1") (pintype "passive"))
      (node (ref "TP1") (pin "P$1") (pinfunction "P$1_P$1") (pintype "bidirectional"))
      (node (ref "U3") (pin "46") (pinfunction "PA31/I15/SERCOM1.3/SWDIO_46") (pintype "bidirectional"))
    )
    (net (code "46") (name "TS") (class "Default")
      (node (ref "R9") (pin "1") (pinfunction "1_1") (pintype "passive"))
      (node (ref "RT1") (pin "2") (pinfunction "2_2") (pintype "passive"))
      (node (ref "U3") (pin "47") (pinfunction "PB02/I2/AIN14/SERCOM5.0/PTCX20+Y20_47") (pintype "bidirectional"))
    )
    (net (code "47") (name "TX") (class "Default")
      (node (ref "JP2") (pin "8") (pinfunction "8_8") (pintype "passive"))
      (node (ref "U3") (pin "25") (pinfunction "PA16/I2C/I0/SERCOM1.0+3.1/PTCX10+Y10_25") (pintype "bidirectional"))
    )
    (net (code "48") (name "USBID") (class "Default")
      (node (ref "J1") (pin "4") (pinfunction "ID_4") (pintype "passive"))
      (node (ref "U3") (pin "32") (pinfunction "PA23/I2C/I7/SERCOM3.1+5.0/SOF/I2SFS1/PTCX17+Y17_32") (pintype "bidirectional"))
    )
    (net (code "49") (name "USB_N") (class "Default")
      (node (ref "J1") (pin "2") (pinfunction "D-_2") (pintype "passive"))
      (node (ref "U3") (pin "33") (pinfunction "PA24/I8/SERCOM3+5.2/D-_33") (pintype "bidirectional"))
    )
    (net (code "50") (name "USB_P") (class "Default")
      (node (ref "J1") (pin "3") (pinfunction "D+_3") (pintype "passive"))
      (node (ref "U3") (pin "34") (pinfunction "PA25/19/SERCOM3+5.3/D+_34") (pintype "bidirectional"))
    )
    (net (code "51") (name "V+") (class "Default")
      (node (ref "C1") (pin "1") (pinfunction "1_1") (pintype "passive"))
      (node (ref "D1") (pin "C") (pinfunction "C_C") (pintype "passive"))
      (node (ref "Q1") (pin "2") (pinfunction "S_2") (pintype "passive"))
      (node (ref "R2") (pin "8") (pinfunction "2_8") (pintype "passive"))
      (node (ref "U1") (pin "1") (pinfunction "IN_1") (pintype "power_in"))
    )
    (net (code "52") (name "VBACKUP") (class "Default")
      (node (ref "B1") (pin "+") (pinfunction "+_+") (pintype "passive"))
      (node (ref "SJ2") (pin "2") (pinfunction "2_2") (pintype "passive"))
      (node (ref "U5") (pin "14") (pinfunction "VBAT_14") (pintype "power_in"))
    )
    (net (code "53") (name "VBAT") (class "Default")
      (node (ref "C4") (pin "1") (pinfunction "1_1") (pintype "passive"))
      (node (ref "J2") (pin "1") (pinfunction "1_1") (pintype "passive"))
      (node (ref "Q1") (pin "3") (pinfunction "D_3") (pintype "passive"))
      (node (ref "R1") (pin "7") (pinfunction "2_7") (pintype "passive"))
      (node (ref "U2") (pin "3") (pinfunction "VBAT_3") (pintype "power_in"))
    )
    (net (code "54") (name "VBUS") (class "Default")
      (node (ref "CHG") (pin "A") (pinfunction "A_A") (pintype "passive"))
      (node (ref "D1") (pin "A") (pinfunction "A_A") (pintype "passive"))
      (node (ref "J1") (pin "1") (pinfunction "VUSB_1") (pintype "passive"))
      (node (ref "Q1") (pin "1") (pinfunction "G_1") (pintype "passive"))
      (node (ref "R1") (pin "8") (pinfunction "2_8") (pintype "passive"))
      (node (ref "U2") (pin "4") (pinfunction "VDD_4") (pintype "power_in"))
    )
    (net (code "55") (name "VSW") (class "Default")
      (node (ref "U3") (pin "43") (pinfunction "VSW_43") (pintype "power_in"))
    )
    (net (code "56") (name "XIN32") (class "Default")
      (node (ref "C11") (pin "1") (pinfunction "1_1") (pintype "passive"))
      (node (ref "U3") (pin "1") (pinfunction "PA00/EINT0/SERCOM1.0_1") (pintype "bidirectional"))
      (node (ref "X1") (pin "P$2") (pinfunction "P$2_P$2") (pintype "bidirectional"))
    )
    (net (code "57") (name "XOUT32") (class "Default")
      (node (ref "C12") (pin "1") (pinfunction "1_1") (pintype "passive"))
      (node (ref "U3") (pin "2") (pinfunction "PA01/EINT1/SERCOM1.1_2") (pintype "bidirectional"))
      (node (ref "X1") (pin "P$1") (pinfunction "P$1_P$1") (pintype "bidirectional"))
    )
    (net (code "58") (name "unconnected-(NEOPIX-DO-Pad3)") (class "Default")
      (node (ref "NEOPIX") (pin "3") (pinfunction "DO_3") (pintype "output"))
    )
    (net (code "59") (name "unconnected-(R1D-1-Pad4)") (class "Default")
      (node (ref "R1") (pin "4") (pinfunction "1_4") (pintype "passive"))
    )
    (net (code "60") (name "unconnected-(R2C-1-Pad3)") (class "Default")
      (node (ref "R2") (pin "3") (pinfunction "1_3") (pintype "passive"))
    )
    (net (code "61") (name "unconnected-(R2C-2-Pad6)") (class "Default")
      (node (ref "R2") (pin "6") (pinfunction "2_6") (pintype "passive"))
    )
    (net (code "62") (name "unconnected-(S1-Pad1)") (class "Default")
      (node (ref "S1") (pin "1") (pinfunction "1_1") (pintype "passive"))
    )
    (net (code "63") (name "unconnected-(U1-P4-Pad4)") (class "Default")
      (node (ref "U1") (pin "4") (pinfunction "P4_4") (pintype "bidirectional"))
    )
    (net (code "64") (name "unconnected-(U3A-PA22{slash}I2C{slash}16{slash}SERCOM3.0+5.1{slash}I2SDI{slash}PTCX16+Y16-Pad31)") (class "Default")
      (node (ref "U3") (pin "31") (pinfunction "PA22/I2C/16/SERCOM3.0+5.1/I2SDI/PTCX16+Y16_31") (pintype "bidirectional"))
    )
    (net (code "65") (name "unconnected-(U5-32KHZ-Pad1)") (class "Default")
      (node (ref "U5") (pin "1") (pinfunction "32KHZ_1") (pintype "output"))
    )
    (net (code "66") (name "unconnected-(U5-NC-Pad5)") (class "Default")
      (node (ref "U5") (pin "5") (pinfunction "NC_5") (pintype "no_connect"))
    )
    (net (code "67") (name "unconnected-(U5-NC1-Pad6)") (class "Default")
      (node (ref "U5") (pin "6") (pinfunction "NC1_6") (pintype "no_connect"))
    )
    (net (code "68") (name "unconnected-(U5-NC2-Pad7)") (class "Default")
      (node (ref "U5") (pin "7") (pinfunction "NC2_7") (pintype "no_connect"))
    )
    (net (code "69") (name "unconnected-(U5-NC3-Pad8)") (class "Default")
      (node (ref "U5") (pin "8") (pinfunction "NC3_8") (pintype "no_connect"))
    )
    (net (code "70") (name "unconnected-(U5-NC4-Pad9)") (class "Default")
      (node (ref "U5") (pin "9") (pinfunction "NC4_9") (pintype "no_connect"))
    )
    (net (code "71") (name "unconnected-(U5-NC5-Pad10)") (class "Default")
      (node (ref "U5") (pin "10") (pinfunction "NC5_10") (pintype "no_connect"))
    )
    (net (code "72") (name "unconnected-(U5-NC6-Pad11)") (class "Default")
      (node (ref "U5") (pin "11") (pinfunction "NC6_11") (pintype "no_connect"))
    )
    (net (code "73") (name "unconnected-(U5-NC7-Pad12)") (class "Default")
      (node (ref "U5") (pin "12") (pinfunction "NC7_12") (pintype "no_connect"))
    )
    (net (code "74") (name "unconnected-(U5-{slash}RST-Pad4)") (class "Default")
      (node (ref "U5") (pin "4") (pinfunction "/RST_4") (pintype "passive"))
    )
    (net (code "75") (name "~{RESET}") (class "Default")
      (node (ref "R3") (pin "8") (pinfunction "2_8") (pintype "passive"))
      (node (ref "RESET") (pin "P$2") (pinfunction "P$2_P$2") (pintype "passive"))
      (node (ref "TP5") (pin "P$1") (pinfunction "P$1_P$1") (pintype "bidirectional"))
      (node (ref "U3") (pin "40") (pinfunction "RESETN_40") (pintype "passive"))
    )
  )
)
